# MCU063A_Emulator_interface.net
KiCad netlist of a schematic drawn in Altium Designer
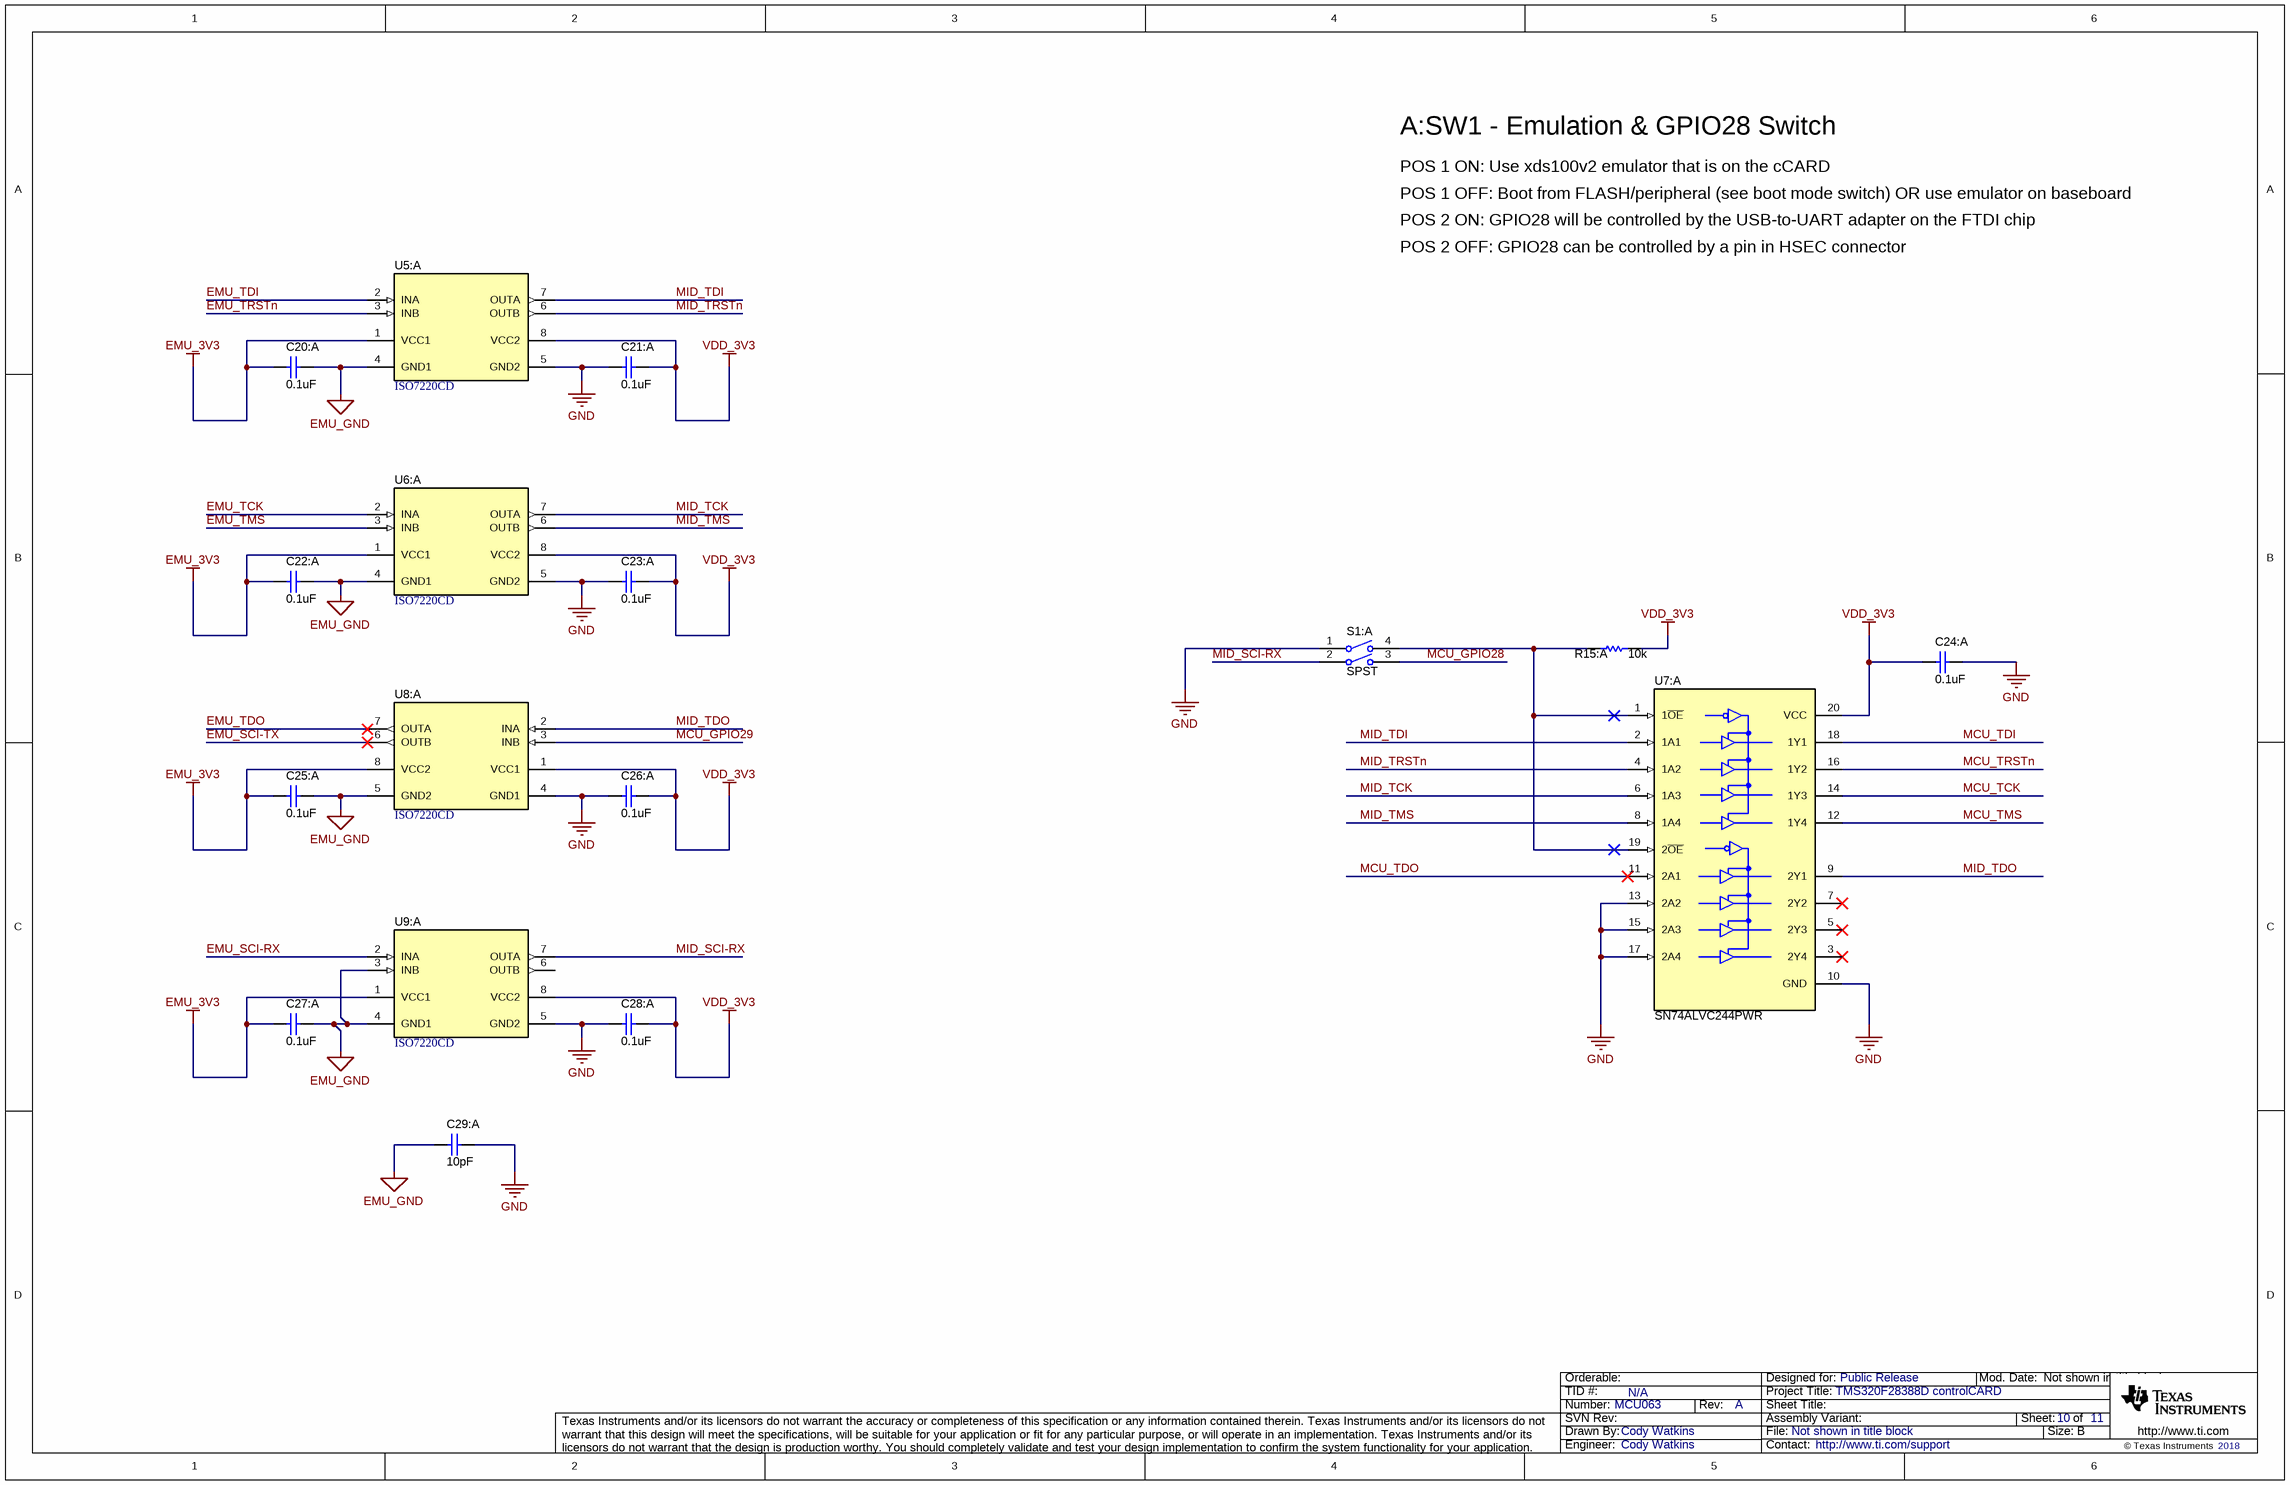
[diagram p0: MCU063A_Emulator_interface.SchDoc]

(export (version "E")
  (design (tool "Eeschema 10.0.6"))
  (components
    (comp (ref "C20:A")
      (value "CL05B104KP5NNNC")
      (footprint "0402")
      (description "CAP, CERM, 0.1 uF, 10 V, +/- 10%, X7R, 0402")
      (fields
        (field (name "VALUEDISPLAYED") "0.1uF")
        (field (name "MANUFACTURER") "Samsung Electro-Mechanics")
        (field (name "PUBLISHER") "Texas Instruments")
      )
      (libsource (lib "Altium Vault - TI") (part "Capacitor"))
    )
    (comp (ref "C21:A")
      (value "CL05B104KP5NNNC")
      (footprint "0402")
      (description "CAP, CERM, 0.1 uF, 10 V, +/- 10%, X7R, 0402")
      (fields
        (field (name "VALUEDISPLAYED") "0.1uF")
        (field (name "MANUFACTURER") "Samsung Electro-Mechanics")
        (field (name "PUBLISHER") "Texas Instruments")
      )
      (libsource (lib "Altium Vault - TI") (part "Capacitor"))
    )
    (comp (ref "C22:A")
      (value "CL05B104KP5NNNC")
      (footprint "0402")
      (description "CAP, CERM, 0.1 uF, 10 V, +/- 10%, X7R, 0402")
      (fields
        (field (name "VALUEDISPLAYED") "0.1uF")
        (field (name "MANUFACTURER") "Samsung Electro-Mechanics")
        (field (name "PUBLISHER") "Texas Instruments")
      )
      (libsource (lib "Altium Vault - TI") (part "Capacitor"))
    )
    (comp (ref "C23:A")
      (value "CL05B104KP5NNNC")
      (footprint "0402")
      (description "CAP, CERM, 0.1 uF, 10 V, +/- 10%, X7R, 0402")
      (fields
        (field (name "VALUEDISPLAYED") "0.1uF")
        (field (name "MANUFACTURER") "Samsung Electro-Mechanics")
        (field (name "PUBLISHER") "Texas Instruments")
      )
      (libsource (lib "Altium Vault - TI") (part "Capacitor"))
    )
    (comp (ref "C24:A")
      (value "CL05B104KP5NNNC")
      (footprint "0402")
      (description "CAP, CERM, 0.1 uF, 10 V, +/- 10%, X7R, 0402")
      (fields
        (field (name "VALUEDISPLAYED") "0.1uF")
        (field (name "MANUFACTURER") "Samsung Electro-Mechanics")
        (field (name "PUBLISHER") "Texas Instruments")
      )
      (libsource (lib "Altium Vault - TI") (part "Capacitor"))
    )
    (comp (ref "C25:A")
      (value "CL05B104KP5NNNC")
      (footprint "0402")
      (description "CAP, CERM, 0.1 uF, 10 V, +/- 10%, X7R, 0402")
      (fields
        (field (name "VALUEDISPLAYED") "0.1uF")
        (field (name "MANUFACTURER") "Samsung Electro-Mechanics")
        (field (name "PUBLISHER") "Texas Instruments")
      )
      (libsource (lib "Altium Vault - TI") (part "Capacitor"))
    )
    (comp (ref "C26:A")
      (value "CL05B104KP5NNNC")
      (footprint "0402")
      (description "CAP, CERM, 0.1 uF, 10 V, +/- 10%, X7R, 0402")
      (fields
        (field (name "VALUEDISPLAYED") "0.1uF")
        (field (name "MANUFACTURER") "Samsung Electro-Mechanics")
        (field (name "PUBLISHER") "Texas Instruments")
      )
      (libsource (lib "Altium Vault - TI") (part "Capacitor"))
    )
    (comp (ref "C27:A")
      (value "CL05B104KP5NNNC")
      (footprint "0402")
      (description "CAP, CERM, 0.1 uF, 10 V, +/- 10%, X7R, 0402")
      (fields
        (field (name "VALUEDISPLAYED") "0.1uF")
        (field (name "MANUFACTURER") "Samsung Electro-Mechanics")
        (field (name "PUBLISHER") "Texas Instruments")
      )
      (libsource (lib "Altium Vault - TI") (part "Capacitor"))
    )
    (comp (ref "C28:A")
      (value "CL05B104KP5NNNC")
      (footprint "0402")
      (description "CAP, CERM, 0.1 uF, 10 V, +/- 10%, X7R, 0402")
      (fields
        (field (name "VALUEDISPLAYED") "0.1uF")
        (field (name "MANUFACTURER") "Samsung Electro-Mechanics")
        (field (name "PUBLISHER") "Texas Instruments")
      )
      (libsource (lib "Altium Vault - TI") (part "Capacitor"))
    )
    (comp (ref "C29:A")
      (value "C1812C100JHGACTU")
      (footprint "1812_180")
      (description "CAP, CERM, 10 pF, 3000 V,+/- 5%, C0G/NP0, AEC-Q200 Grade 1, 1812")
      (fields (field (name "MANUFACTURER") "Kemet") (field (name "VALUEDISPLAYED") "10pF"))
      (libsource (lib "Altium Vault - TI") (part "Capacitor"))
    )
    (comp (ref "R15:A")
      (value "CRCW040210K0JNED")
      (footprint "0402")
      (description "RES, 10 k, 5%, 0.063 W, AEC-Q200 Grade 0, 0402")
      (fields (field (name "VALUEDISPLAYED") "10k") (field (name "MANUFACTURER") "Vishay-Dale"))
      (libsource (lib "Altium Vault - TI") (part "Resistor"))
    )
    (comp (ref "S1:A")
      (value "218-2LPST")
      (footprint "SW_218-2LP")
      (description "Switch, SPST, 2 Pos, 25mA, 24VDC, SMD")
      (fields
        (field (name "MANUFACTURER") "CTS Electrocomponents")
        (field (name "CIRCUIT") "SPST")
        (field (name "PUBLISHER") "Texas Instruments")
      )
      (libsource (lib "Altium Vault - TI") (part "SW_2SPST"))
    )
    (comp (ref "U5:A")
      (value "ISO7220CD")
      (footprint "D0008B_N")
      (fields (field (name "MANUFACTURER") "Texas Instruments"))
      (libsource (lib "") (part "TI-ISO7220C-SOIC_D-8_1"))
    )
    (comp (ref "U6:A")
      (value "ISO7220CD")
      (footprint "D0008B_N")
      (fields (field (name "MANUFACTURER") "Texas Instruments"))
      (libsource (lib "") (part "TI-ISO7220C-SOIC_D-8_1"))
    )
    (comp (ref "U7:A")
      (value "SN74ALVC244PWR")
      (footprint "PW0020A_N")
      (description "Octal Buffer/Driver With 3-State OUtputs, PW0020A (TSSOP-20)")
      (fields
        (field (name "MANUFACTURER") "Texas Instruments")
        (field (name "GENERIC PART NUMBER") "SN74ALVC244")
      )
      (libsource (lib "Altium Vault - TI") (part "SN74ALVC244PW"))
    )
    (comp (ref "U8:A")
      (value "ISO7220CD")
      (footprint "D0008B_N")
      (fields (field (name "MANUFACTURER") "Texas Instruments"))
      (libsource (lib "Altium Vault - TI") (part "TI-ISO7220C-SOIC_D-8"))
    )
    (comp (ref "U9:A")
      (value "ISO7220CD")
      (footprint "D0008B_N")
      (fields (field (name "MANUFACTURER") "Texas Instruments"))
      (libsource (lib "") (part "TI-ISO7220C-SOIC_D-8_1"))
    )
  )
  (nets
    (net (code "1") (name "/EMU_SCI-RX") (class "Default")
      (node (ref "U9:A") (pin "2") (pinfunction "INA_2") (pintype "input"))
    )
    (net (code "2") (name "/EMU_SCI-TX") (class "Default")
      (node (ref "U8:A") (pin "6") (pinfunction "OUTB_6") (pintype "output+no_connect"))
    )
    (net (code "3") (name "/EMU_TCK") (class "Default")
      (node (ref "U6:A") (pin "2") (pinfunction "INA_2") (pintype "input"))
    )
    (net (code "4") (name "/EMU_TDI") (class "Default")
      (node (ref "U5:A") (pin "2") (pinfunction "INA_2") (pintype "input"))
    )
    (net (code "5") (name "/EMU_TDO") (class "Default")
      (node (ref "U8:A") (pin "7") (pinfunction "OUTA_7") (pintype "output+no_connect"))
    )
    (net (code "6") (name "/EMU_TMS") (class "Default")
      (node (ref "U6:A") (pin "3") (pinfunction "INB_3") (pintype "input"))
    )
    (net (code "7") (name "/EMU_TRSTn") (class "Default")
      (node (ref "U5:A") (pin "3") (pinfunction "INB_3") (pintype "input"))
    )
    (net (code "8") (name "/MCU_GPIO28") (class "Default")
      (node (ref "S1:A") (pin "3") (pinfunction "3_3") (pintype "passive"))
    )
    (net (code "9") (name "/MCU_GPIO29") (class "Default")
      (node (ref "U8:A") (pin "3") (pinfunction "INB_3") (pintype "input"))
    )
    (net (code "10") (name "/MCU_TCK") (class "Default")
      (node (ref "U7:A") (pin "14") (pinfunction "1Y3_14") (pintype "tri_state"))
    )
    (net (code "11") (name "/MCU_TDI") (class "Default")
      (node (ref "U7:A") (pin "18") (pinfunction "1Y1_18") (pintype "tri_state"))
    )
    (net (code "12") (name "/MCU_TDO") (class "Default")
      (node (ref "U7:A") (pin "11") (pinfunction "2A1_11") (pintype "input+no_connect"))
    )
    (net (code "13") (name "/MCU_TMS") (class "Default")
      (node (ref "U7:A") (pin "12") (pinfunction "1Y4_12") (pintype "tri_state"))
    )
    (net (code "14") (name "/MCU_TRSTn") (class "Default")
      (node (ref "U7:A") (pin "16") (pinfunction "1Y2_16") (pintype "tri_state"))
    )
    (net (code "15") (name "/MID_SCI-RX") (class "Default")
      (node (ref "S1:A") (pin "2") (pinfunction "2_2") (pintype "passive"))
      (node (ref "U9:A") (pin "7") (pinfunction "OUTA_7") (pintype "output"))
    )
    (net (code "16") (name "/MID_TCK") (class "Default")
      (node (ref "U6:A") (pin "7") (pinfunction "OUTA_7") (pintype "output"))
      (node (ref "U7:A") (pin "6") (pinfunction "1A3_6") (pintype "input"))
    )
    (net (code "17") (name "/MID_TDI") (class "Default")
      (node (ref "U5:A") (pin "7") (pinfunction "OUTA_7") (pintype "output"))
      (node (ref "U7:A") (pin "2") (pinfunction "1A1_2") (pintype "input"))
    )
    (net (code "18") (name "/MID_TDO") (class "Default")
      (node (ref "U7:A") (pin "9") (pinfunction "2Y1_9") (pintype "tri_state"))
      (node (ref "U8:A") (pin "2") (pinfunction "INA_2") (pintype "input"))
    )
    (net (code "19") (name "/MID_TMS") (class "Default")
      (node (ref "U6:A") (pin "6") (pinfunction "OUTB_6") (pintype "output"))
      (node (ref "U7:A") (pin "8") (pinfunction "1A4_8") (pintype "input"))
    )
    (net (code "20") (name "/MID_TRSTn") (class "Default")
      (node (ref "U5:A") (pin "6") (pinfunction "OUTB_6") (pintype "output"))
      (node (ref "U7:A") (pin "4") (pinfunction "1A2_4") (pintype "input"))
    )
    (net (code "21") (name "EMU_3V3") (class "Default")
      (node (ref "C20:A") (pin "2") (pinfunction "2_2") (pintype "passive"))
      (node (ref "C22:A") (pin "2") (pinfunction "2_2") (pintype "passive"))
      (node (ref "C25:A") (pin "2") (pinfunction "2_2") (pintype "passive"))
      (node (ref "C27:A") (pin "2") (pinfunction "2_2") (pintype "passive"))
      (node (ref "U5:A") (pin "1") (pinfunction "VCC1_1") (pintype "power_in"))
      (node (ref "U6:A") (pin "1") (pinfunction "VCC1_1") (pintype "power_in"))
      (node (ref "U8:A") (pin "8") (pinfunction "VCC2_8") (pintype "power_in"))
      (node (ref "U9:A") (pin "1") (pinfunction "VCC1_1") (pintype "power_in"))
    )
    (net (code "22") (name "EMU_GND") (class "Default")
      (node (ref "C20:A") (pin "1") (pinfunction "1_1") (pintype "passive"))
      (node (ref "C22:A") (pin "1") (pinfunction "1_1") (pintype "passive"))
      (node (ref "C25:A") (pin "1") (pinfunction "1_1") (pintype "passive"))
      (node (ref "C27:A") (pin "1") (pinfunction "1_1") (pintype "passive"))
      (node (ref "C29:A") (pin "2") (pinfunction "2_2") (pintype "passive"))
      (node (ref "U5:A") (pin "4") (pinfunction "GND1_4") (pintype "power_in"))
      (node (ref "U6:A") (pin "4") (pinfunction "GND1_4") (pintype "power_in"))
      (node (ref "U8:A") (pin "5") (pinfunction "GND2_5") (pintype "power_in"))
      (node (ref "U9:A") (pin "3") (pinfunction "INB_3") (pintype "input"))
      (node (ref "U9:A") (pin "4") (pinfunction "GND1_4") (pintype "power_in"))
    )
    (net (code "23") (name "GND") (class "Default")
      (node (ref "C21:A") (pin "2") (pinfunction "2_2") (pintype "passive"))
      (node (ref "C23:A") (pin "2") (pinfunction "2_2") (pintype "passive"))
      (node (ref "C24:A") (pin "1") (pinfunction "1_1") (pintype "passive"))
      (node (ref "C26:A") (pin "2") (pinfunction "2_2") (pintype "passive"))
      (node (ref "C28:A") (pin "2") (pinfunction "2_2") (pintype "passive"))
      (node (ref "C29:A") (pin "1") (pinfunction "1_1") (pintype "passive"))
      (node (ref "S1:A") (pin "1") (pinfunction "1_1") (pintype "passive"))
      (node (ref "U5:A") (pin "5") (pinfunction "GND2_5") (pintype "power_in"))
      (node (ref "U6:A") (pin "5") (pinfunction "GND2_5") (pintype "power_in"))
      (node (ref "U7:A") (pin "10") (pinfunction "GND_10") (pintype "power_in"))
      (node (ref "U7:A") (pin "13") (pinfunction "2A2_13") (pintype "input"))
      (node (ref "U7:A") (pin "15") (pinfunction "2A3_15") (pintype "input"))
      (node (ref "U7:A") (pin "17") (pinfunction "2A4_17") (pintype "input"))
      (node (ref "U8:A") (pin "4") (pinfunction "GND1_4") (pintype "power_in"))
      (node (ref "U9:A") (pin "5") (pinfunction "GND2_5") (pintype "power_in"))
    )
    (net (code "24") (name "Net-(U7:A-1~{OE})") (class "Default")
      (node (ref "R15:A") (pin "1") (pinfunction "1_1") (pintype "passive"))
      (node (ref "S1:A") (pin "4") (pinfunction "4_4") (pintype "passive"))
      (node (ref "U7:A") (pin "1") (pinfunction "1~{OE}_1") (pintype "input"))
      (node (ref "U7:A") (pin "19") (pinfunction "2~{OE}_19") (pintype "input"))
    )
    (net (code "25") (name "VDD_3V3") (class "Default")
      (node (ref "C21:A") (pin "1") (pinfunction "1_1") (pintype "passive"))
      (node (ref "C23:A") (pin "1") (pinfunction "1_1") (pintype "passive"))
      (node (ref "C24:A") (pin "2") (pinfunction "2_2") (pintype "passive"))
      (node (ref "C26:A") (pin "1") (pinfunction "1_1") (pintype "passive"))
      (node (ref "C28:A") (pin "1") (pinfunction "1_1") (pintype "passive"))
      (node (ref "R15:A") (pin "2") (pinfunction "2_2") (pintype "passive"))
      (node (ref "U5:A") (pin "8") (pinfunction "VCC2_8") (pintype "power_in"))
      (node (ref "U6:A") (pin "8") (pinfunction "VCC2_8") (pintype "power_in"))
      (node (ref "U7:A") (pin "20") (pinfunction "VCC_20") (pintype "power_in"))
      (node (ref "U8:A") (pin "1") (pinfunction "VCC1_1") (pintype "power_in"))
      (node (ref "U9:A") (pin "8") (pinfunction "VCC2_8") (pintype "power_in"))
    )
    (net (code "26") (name "unconnected-(U7:A-2Y2-Pad7)") (class "Default")
      (node (ref "U7:A") (pin "7") (pinfunction "2Y2_7") (pintype "tri_state+no_connect"))
    )
    (net (code "27") (name "unconnected-(U7:A-2Y3-Pad5)") (class "Default")
      (node (ref "U7:A") (pin "5") (pinfunction "2Y3_5") (pintype "tri_state+no_connect"))
    )
    (net (code "28") (name "unconnected-(U7:A-2Y4-Pad3)") (class "Default")
      (node (ref "U7:A") (pin "3") (pinfunction "2Y4_3") (pintype "tri_state+no_connect"))
    )
    (net (code "29") (name "unconnected-(U9:A-OUTB-Pad6)") (class "Default")
      (node (ref "U9:A") (pin "6") (pinfunction "OUTB_6") (pintype "output"))
    )
  )
)
